# Design1.net
KiCad netlist of a schematic drawn in Altium Designer
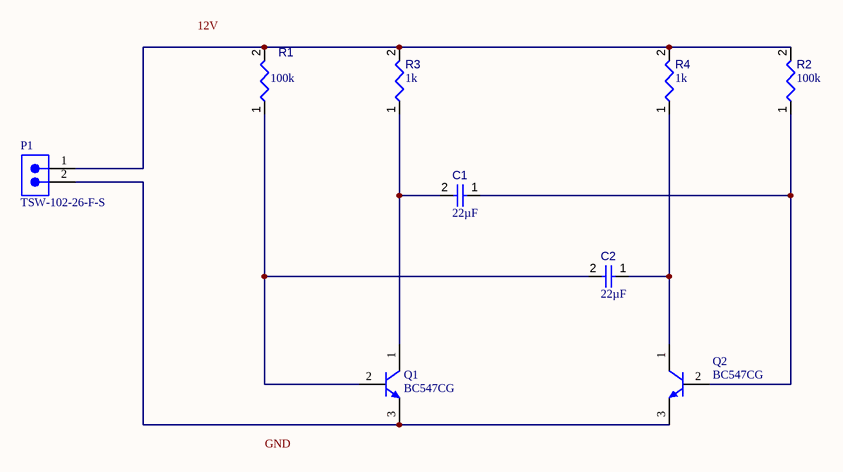
[diagram p0: Design1.SchDoc]

(export (version "E")
  (design (tool "Eeschema 10.0.6"))
  (components
    (comp (ref "C1")
      (value "22µF")
      (footprint "CAPC0805(2012)145_L")
      (description "Chip Capacitor, 22µF +/-5%, 16V, 0603, Thickness 1.45 mm")
      (fields (field (name "TOLERANCE") "5%") (field (name "Comment") "Capacitor 22µF +/-40% 16V 0805"))
      (libsource (lib "Student") (part "CAP-NP-2"))
    )
    (comp (ref "C2")
      (value "22µF")
      (footprint "CAPC0805(2012)145_L")
      (description "Chip Capacitor, 22µF +/-5%, 16V, 0603, Thickness 1.45 mm")
      (fields (field (name "TOLERANCE") "5%") (field (name "Comment") "Capacitor 22µF +/-40% 16V 0805"))
      (libsource (lib "Student") (part "CAP-NP-2"))
    )
    (comp (ref "P1")
      (value "TSW-102-26-F-S")
      (footprint "SMTC-TSW-102-26-XX-S")
      (description "0.025\" SQ Post Header, Through-hole, Vertical, -55 to 125 degC, 2.54 mm Pitch, 2-Pin, Male, RoHS")
      (fields (field (name "MANUFACTURER") "Samtec"))
      (libsource (lib "Altium Content Vault") (part "SMTC-TSW-102-X-X-S-X"))
    )
    (comp (ref "Q1")
      (value "BC547CG")
      (footprint "ONSC-TO-92-3-29-11")
      (description "Amplifier Transistor, NPN Silicon, 3-Pin TO-92, Pb-Free, Bulk Box")
      (fields (field (name "MANUFACTURER") "On Semiconductor"))
      (libsource (lib "Altium Content Vault") (part "ONSC-NPN-C1B2E3-3"))
    )
    (comp (ref "Q2")
      (value "BC547CG")
      (footprint "ONSC-TO-92-3-29-11")
      (description "Amplifier Transistor, NPN Silicon, 3-Pin TO-92, Pb-Free, Bulk Box")
      (fields (field (name "MANUFACTURER") "On Semiconductor"))
      (libsource (lib "Altium Content Vault") (part "ONSC-NPN-C1B2E3-3"))
    )
    (comp (ref "R1")
      (value "Resistor 1k +/-5% 0402 63 mW")
      (footprint "RESC1005X40X25ML10T10")
      (description "Chip Resistor, 1 KOhm, +/- 5%, 0.063 W, -55 to 155 degC, 0402 (1005 Metric)")
      (fields (field (name "TOLERANCE") "5%") (field (name "R1") "100k") (field (name "POWER") "63mW"))
      (libsource (lib "Student") (part "RES-2"))
    )
    (comp (ref "R2")
      (value "100k")
      (footprint "RESC1005X40X25ML10T10")
      (description "Chip Resistor, 1 KOhm, +/- 5%, 0.063 W, -55 to 155 degC, 0402 (1005 Metric)")
      (fields (field (name "TOLERANCE") "5%") (field (name "POWER") "63mW"))
      (libsource (lib "Student") (part "RES-2"))
    )
    (comp (ref "R3")
      (value "1k")
      (footprint "RESC1005X40X25ML10T10")
      (description "Chip Resistor, 1 KOhm, +/- 5%, 0.063 W, -55 to 155 degC, 0402 (1005 Metric)")
      (fields (field (name "TOLERANCE") "5%") (field (name "POWER") "63mW"))
      (libsource (lib "Student") (part "RES-2"))
    )
    (comp (ref "R4")
      (value "1k")
      (footprint "RESC1005X40X25ML10T10")
      (description "Chip Resistor, 1 KOhm, +/- 5%, 0.063 W, -55 to 155 degC, 0402 (1005 Metric)")
      (fields (field (name "TOLERANCE") "5%") (field (name "POWER") "63mW"))
      (libsource (lib "Student") (part "RES-2"))
    )
  )
  (nets
    (net (code "3") (name "Net-(P1-Pad1)") (class "Default")
      (node (ref "P1") (pin "1") (pinfunction "1_1") (pintype "passive"))
      (node (ref "R1") (pin "2") (pinfunction "2_2") (pintype "passive"))
      (node (ref "R2") (pin "2") (pinfunction "2_2") (pintype "passive"))
      (node (ref "R3") (pin "2") (pinfunction "2_2") (pintype "passive"))
      (node (ref "R4") (pin "2") (pinfunction "2_2") (pintype "passive"))
    )
    (net (code "4") (name "Net-(Q1-B)") (class "Default")
      (node (ref "C2") (pin "2") (pinfunction "2_2") (pintype "passive"))
      (node (ref "Q1") (pin "2") (pinfunction "B_2") (pintype "passive"))
      (node (ref "R1") (pin "1") (pinfunction "1_1") (pintype "passive"))
    )
    (net (code "5") (name "Net-(Q1-C)") (class "Default")
      (node (ref "C1") (pin "2") (pinfunction "2_2") (pintype "passive"))
      (node (ref "Q1") (pin "1") (pinfunction "C_1") (pintype "passive"))
      (node (ref "R3") (pin "1") (pinfunction "1_1") (pintype "passive"))
    )
    (net (code "6") (name "Net-(Q1-E)") (class "Default")
      (node (ref "P1") (pin "2") (pinfunction "2_2") (pintype "passive"))
      (node (ref "Q1") (pin "3") (pinfunction "E_3") (pintype "passive"))
      (node (ref "Q2") (pin "3") (pinfunction "E_3") (pintype "passive"))
    )
    (net (code "7") (name "Net-(Q2-B)") (class "Default")
      (node (ref "C1") (pin "1") (pinfunction "1_1") (pintype "passive"))
      (node (ref "Q2") (pin "2") (pinfunction "B_2") (pintype "passive"))
      (node (ref "R2") (pin "1") (pinfunction "1_1") (pintype "passive"))
    )
    (net (code "8") (name "Net-(Q2-C)") (class "Default")
      (node (ref "C2") (pin "1") (pinfunction "1_1") (pintype "passive"))
      (node (ref "Q2") (pin "1") (pinfunction "C_1") (pintype "passive"))
      (node (ref "R4") (pin "1") (pinfunction "1_1") (pintype "passive"))
    )
  )
)
